# NCP1402_3_3V_Breakout.net
KiCad netlist of a schematic drawn in EAGLE
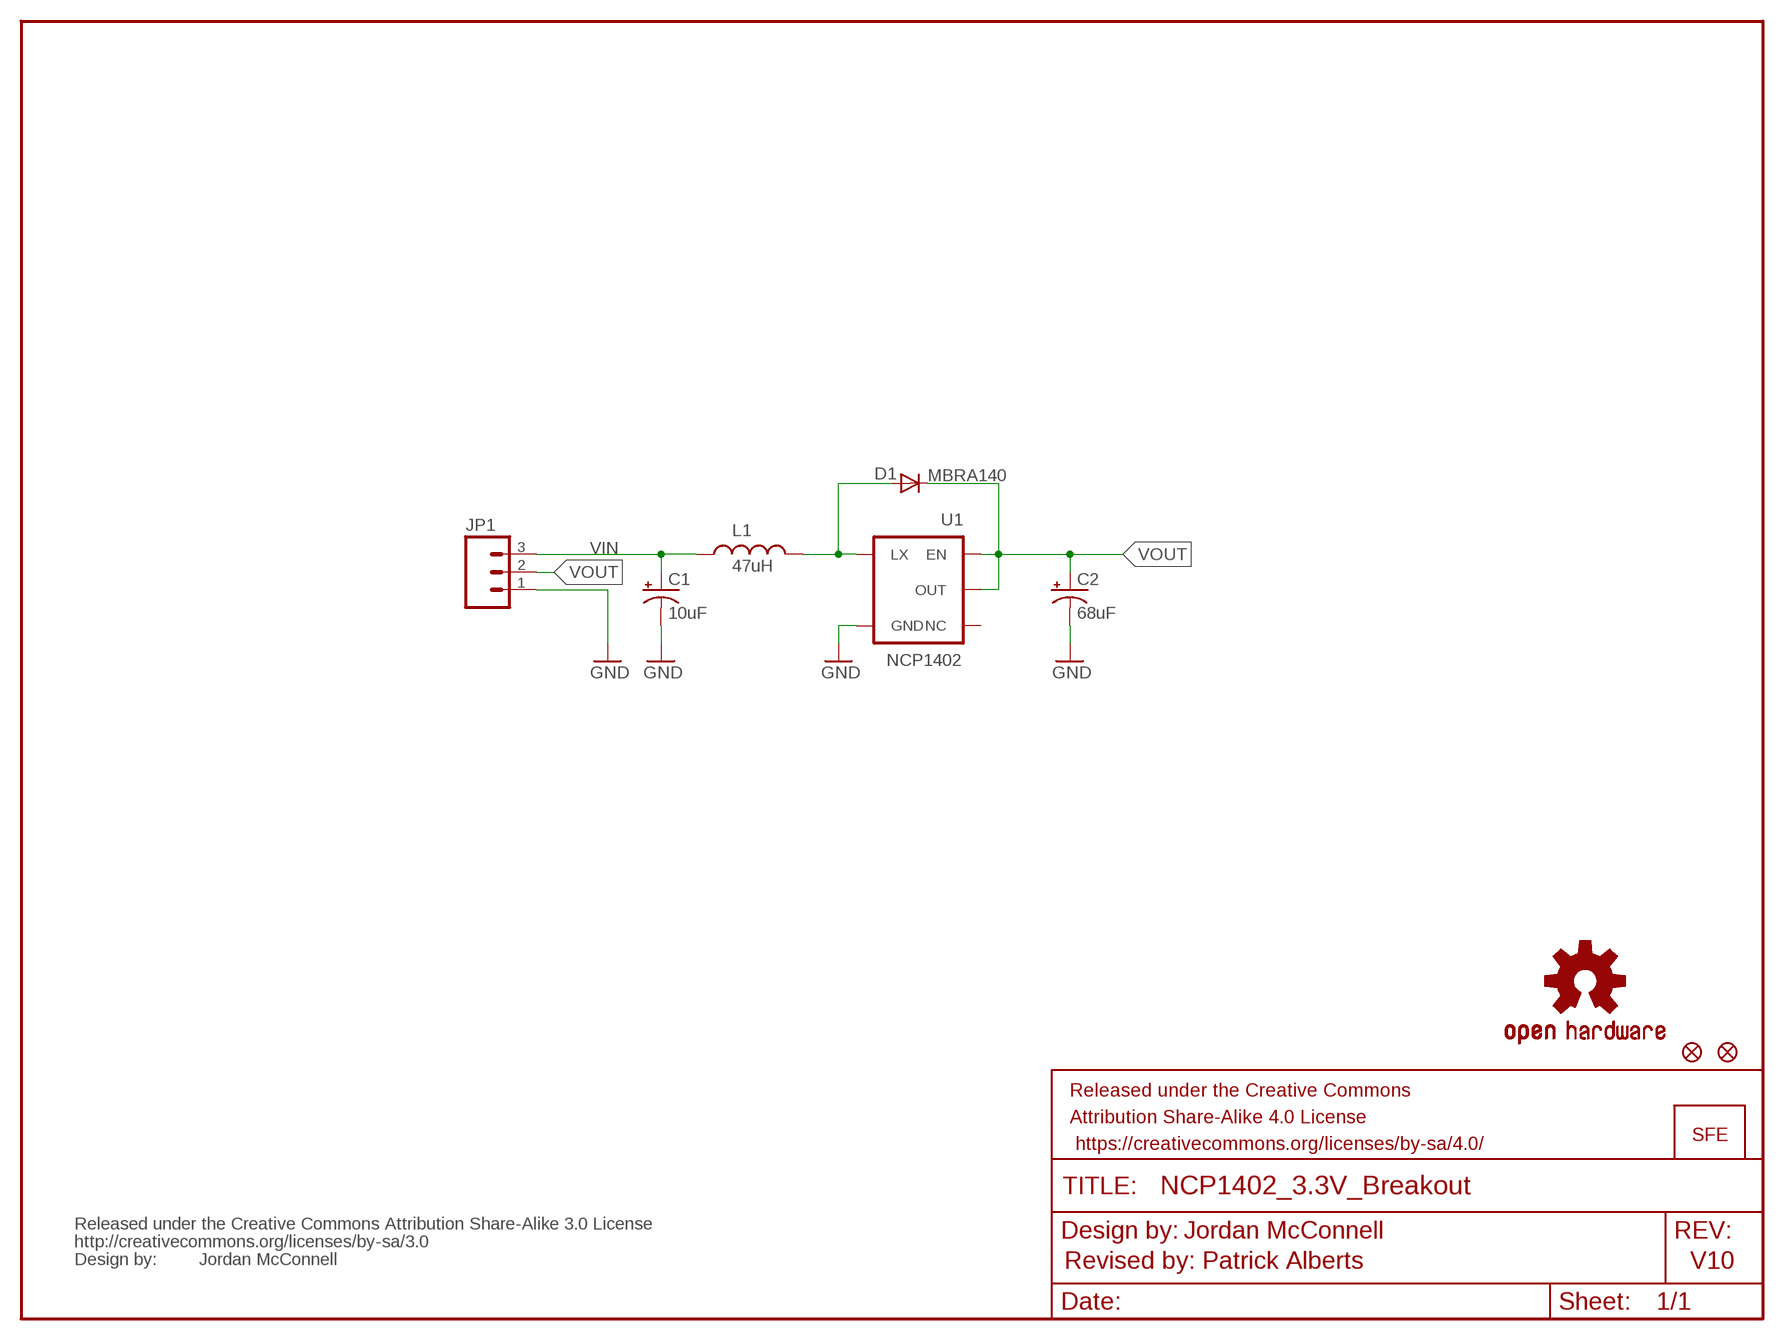
[diagram p0: schematic, sheet 1]

(export (version "E")
  (design (tool "Eeschema 10.0.6"))
  (components
    (comp (ref "C1")
      (value "10uF")
      (footprint "eagle-import:EIA3216")
      (libsource (lib "eagle-import") (part "CAP_POL1206"))
    )
    (comp (ref "C2")
      (value "68uF")
      (footprint "eagle-import:EIA3528")
      (libsource (lib "eagle-import") (part "CAP_POL3528"))
    )
    (comp (ref "D1")
      (value "MBRA140")
      (footprint "eagle-import:SMA-DIODE")
      (libsource (lib "eagle-import") (part "DIODESMA"))
    )
    (comp (ref "FID1")
      (value "FIDUCIAL1X2")
      (footprint "eagle-import:FIDUCIAL-1X2")
      (libsource (lib "eagle-import") (part "FIDUCIAL1X2"))
    )
    (comp (ref "FID2")
      (value "FIDUCIAL1X2")
      (footprint "eagle-import:FIDUCIAL-1X2")
      (libsource (lib "eagle-import") (part "FIDUCIAL1X2"))
    )
    (comp (ref "FRAME1")
      (value "FRAME-LETTER")
      (footprint "eagle-import:CREATIVE_COMMONS")
      (libsource (lib "eagle-import") (part "FRAME-LETTER"))
    )
    (comp (ref "JP1")
      (value "M03PTH")
      (footprint "eagle-import:1X03")
      (libsource (lib "eagle-import") (part "M03PTH"))
    )
    (comp (ref "JP2")
      (value "LOGO-SFESK")
      (footprint "eagle-import:SFE-LOGO-FLAME")
      (libsource (lib "eagle-import") (part "LOGO-SFESK"))
    )
    (comp (ref "L1")
      (value "47uH")
      (footprint "eagle-import:CR54")
      (libsource (lib "eagle-import") (part "INDUCTORCR54"))
    )
    (comp (ref "U$1")
      (value "OSHW-LOGOS")
      (footprint "eagle-import:OSHW-LOGO-S")
      (libsource (lib "eagle-import") (part "OSHW-LOGOS"))
    )
    (comp (ref "U$2")
      (value "CREATIVE_COMMONS")
      (footprint "eagle-import:CREATIVE_COMMONS")
      (libsource (lib "eagle-import") (part "CREATIVE_COMMONS"))
    )
    (comp (ref "U1")
      (value "NCP1402")
      (footprint "eagle-import:SOT23-5")
      (libsource (lib "eagle-import") (part "V_REG_NCP1400SOT23-5"))
    )
  )
  (nets
    (net (code "1") (name "/VIN") (class "Default")
      (node (ref "C1") (pin "A") (pinfunction "+_A") (pintype "passive"))
      (node (ref "JP1") (pin "3") (pinfunction "3_3") (pintype "passive"))
      (node (ref "L1") (pin "P$1") (pinfunction "1_P$1") (pintype "passive"))
    )
    (net (code "2") (name "GND") (class "Default")
      (node (ref "C1") (pin "C") (pinfunction "-_C") (pintype "passive"))
      (node (ref "C2") (pin "C") (pinfunction "-_C") (pintype "passive"))
      (node (ref "JP1") (pin "1") (pinfunction "1_1") (pintype "passive"))
      (node (ref "U1") (pin "4") (pinfunction "GND_4") (pintype "input"))
    )
    (net (code "3") (name "Net-(L1-2)") (class "Default")
      (node (ref "D1") (pin "A") (pinfunction "A_A") (pintype "passive"))
      (node (ref "L1") (pin "P$2") (pinfunction "2_P$2") (pintype "passive"))
      (node (ref "U1") (pin "5") (pinfunction "LX_5") (pintype "input"))
    )
    (net (code "4") (name "VOUT") (class "Default")
      (node (ref "C2") (pin "A") (pinfunction "+_A") (pintype "passive"))
      (node (ref "D1") (pin "C") (pinfunction "C_C") (pintype "passive"))
      (node (ref "JP1") (pin "2") (pinfunction "2_2") (pintype "passive"))
      (node (ref "U1") (pin "1") (pinfunction "EN_1") (pintype "input"))
      (node (ref "U1") (pin "2") (pinfunction "OUT_2") (pintype "passive"))
    )
    (net (code "5") (name "unconnected-(U1-NC-Pad3)") (class "Default")
      (node (ref "U1") (pin "3") (pinfunction "NC_3") (pintype "input"))
    )
  )
)
